# 3-2.net
KiCad netlist of a schematic drawn in Altium Designer
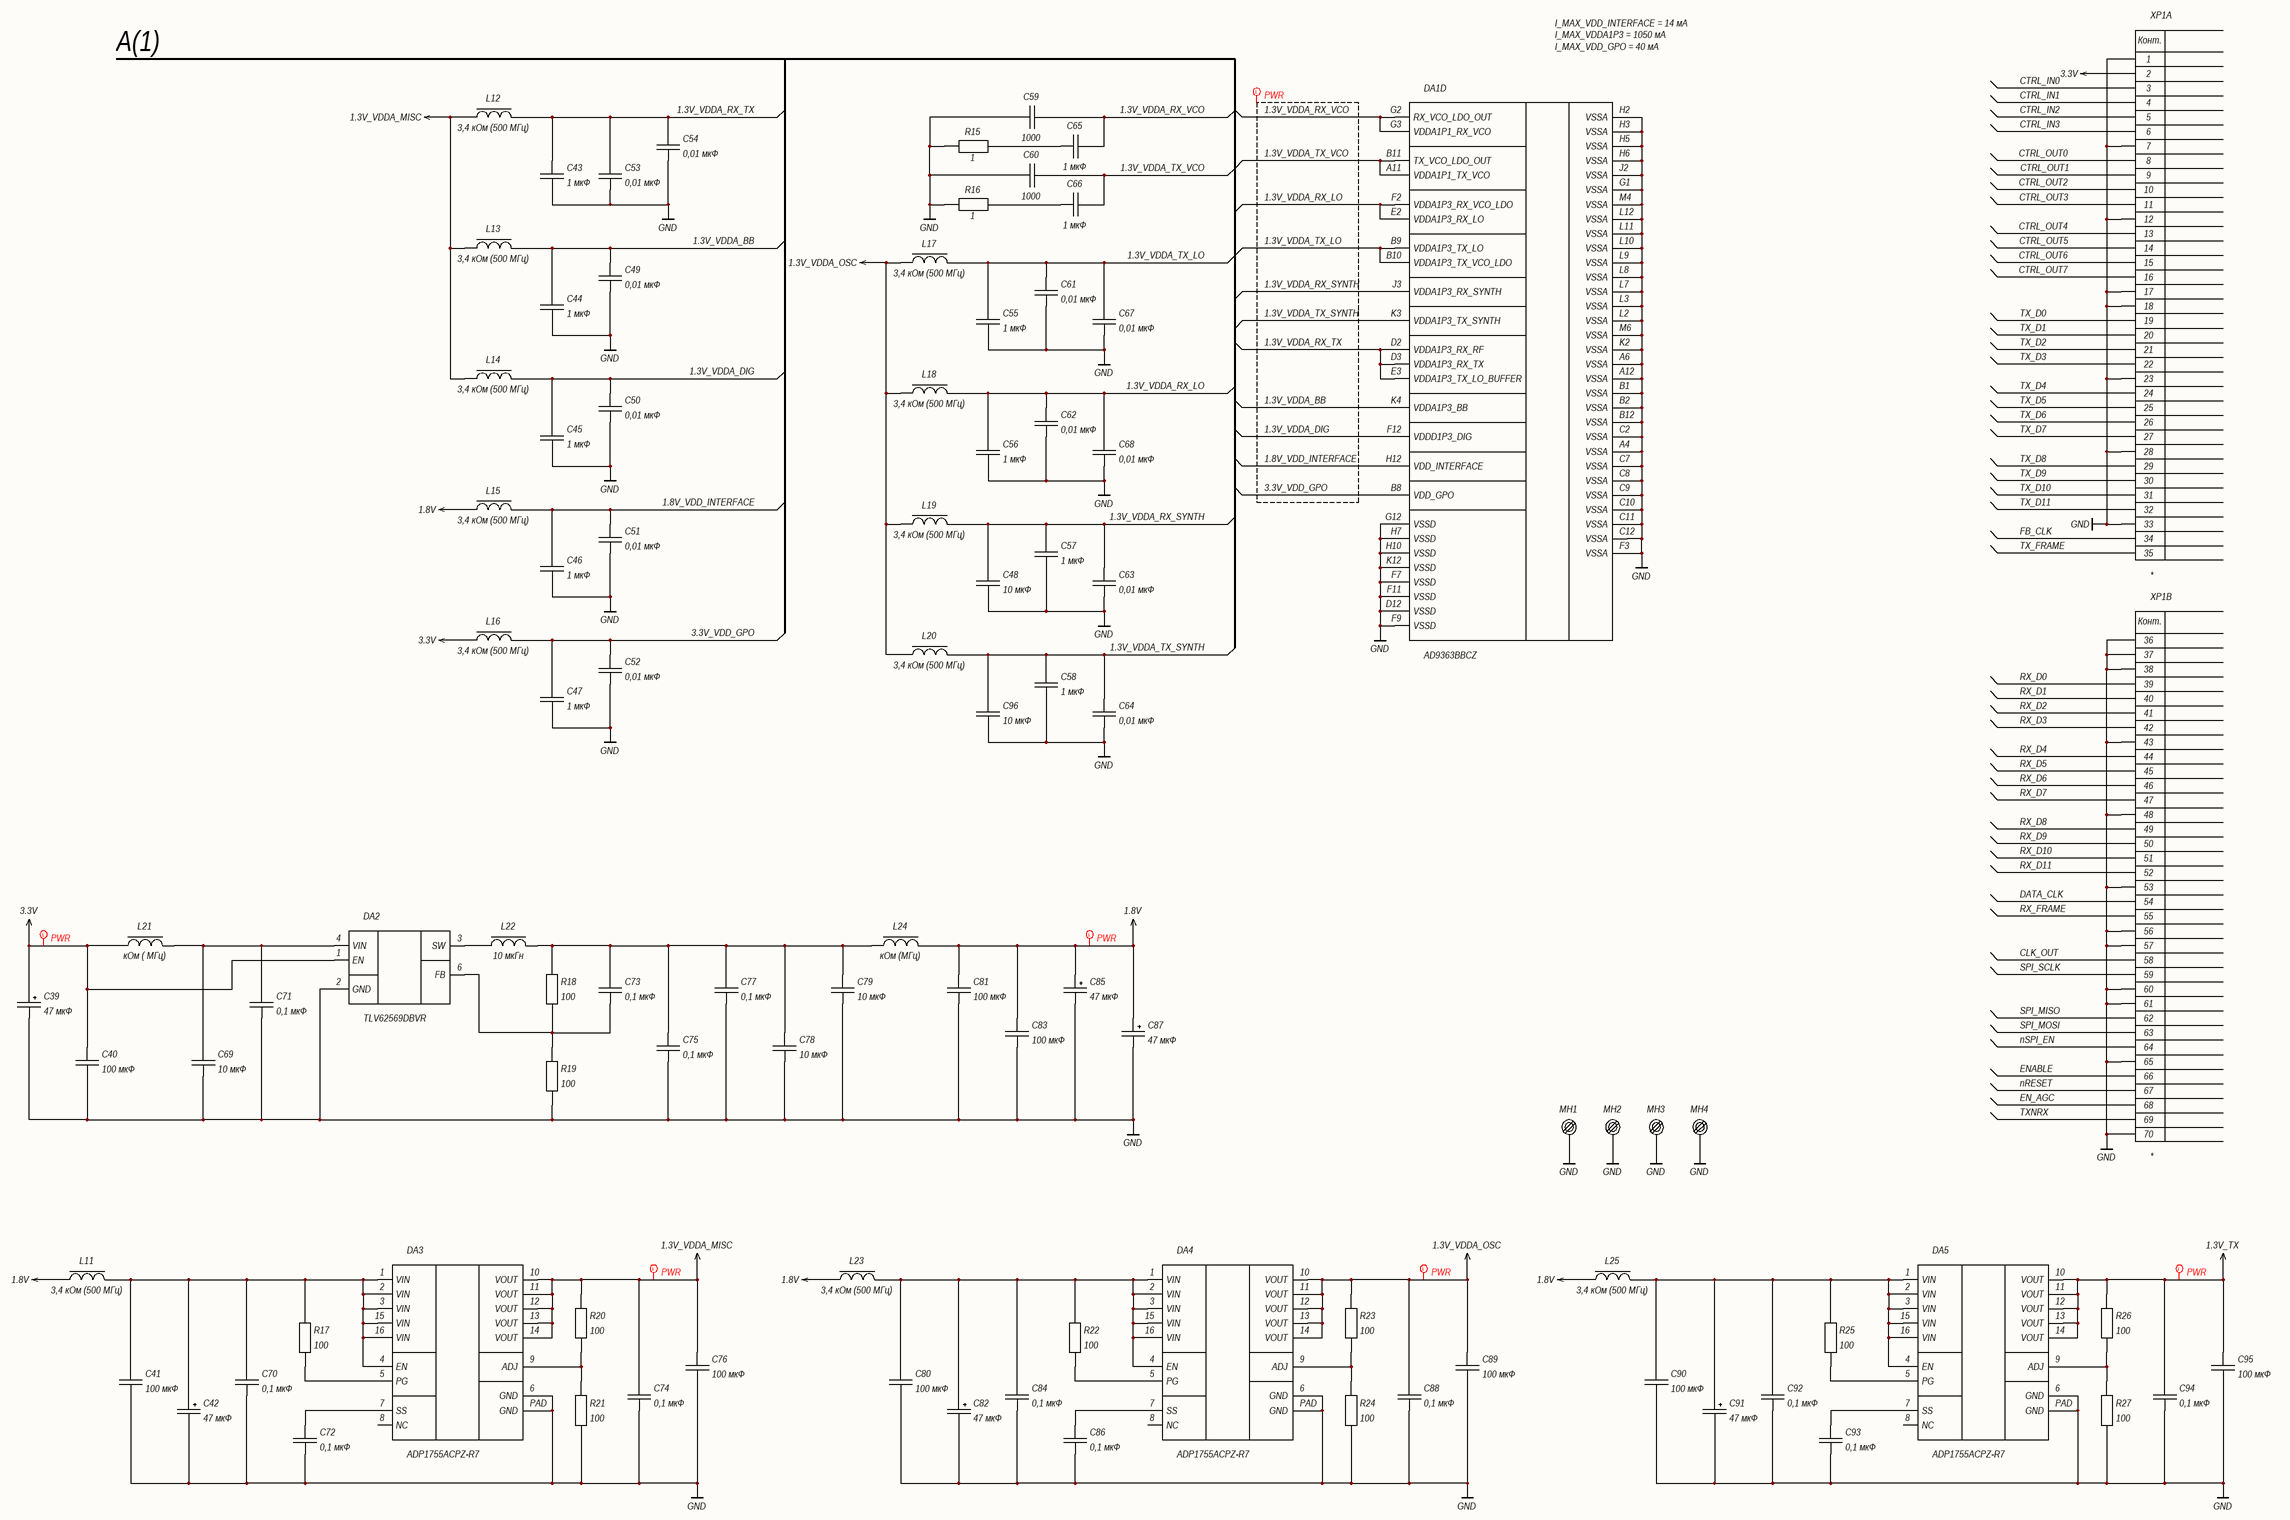
[diagram p0: Э3-2.SchDoc]

(export (version "E")
  (design (tool "Eeschema 10.0.6"))
  (components
    (comp (ref "C39")
      (value "47 мкФ")
      (footprint "TL-A-B-1.8MM")
      (libsource (lib "Capacitors") (part "Polar Ver."))
    )
    (comp (ref "C40")
      (value "100 мкФ")
      (footprint "C1206-B-1.6mm-NO")
      (description "1206 100 мкФ ±20% 6,3 В X5R")
      (libsource (lib "Capacitors") (part "Non Polar Ver."))
    )
    (comp (ref "C41")
      (value "100 мкФ")
      (footprint "C1206-B-1.6mm")
      (description "1206 100 мкФ ±20% 6,3 В X5R")
      (libsource (lib "Capacitors") (part "Non Polar Ver."))
    )
    (comp (ref "C42")
      (value "47 мкФ")
      (footprint "TL-A-B-1.8MM")
      (libsource (lib "Capacitors") (part "Polar Ver."))
    )
    (comp (ref "C43")
      (value "1 мкФ")
      (footprint "C0402-B-0.5mm-NO")
      (description "0402 1 мкФ ±10% 16 В X7R")
      (libsource (lib "Capacitors") (part "Non Polar Ver."))
    )
    (comp (ref "C44")
      (value "1 мкФ")
      (footprint "C0402-B-0.5mm-NO")
      (description "0402 1 мкФ ±10% 16 В X7R")
      (libsource (lib "Capacitors") (part "Non Polar Ver."))
    )
    (comp (ref "C45")
      (value "1 мкФ")
      (footprint "C0402-B-0.5mm-NO")
      (description "0402 1 мкФ ±10% 16 В X7R")
      (libsource (lib "Capacitors") (part "Non Polar Ver."))
    )
    (comp (ref "C46")
      (value "1 мкФ")
      (footprint "C0402-B-0.5mm-NO")
      (description "0402 1 мкФ ±10% 16 В X7R")
      (libsource (lib "Capacitors") (part "Non Polar Ver."))
    )
    (comp (ref "C47")
      (value "1 мкФ")
      (footprint "C0402-B-0.5mm-NO")
      (description "0402 1 мкФ ±10% 16 В X7R")
      (libsource (lib "Capacitors") (part "Non Polar Ver."))
    )
    (comp (ref "C48")
      (value "10 мкФ")
      (footprint "C0603-B-0.8mm-NO")
      (description "0603 10 мкФ ±10% 16 В X7R")
      (libsource (lib "Capacitors") (part "Non Polar Ver."))
    )
    (comp (ref "C49")
      (value "0,01 мкФ")
      (footprint "C0201-B-0.3mm-NO")
      (description "0201 0,01 мкФ ±10% 16 В X7R")
      (libsource (lib "Capacitors") (part "Non Polar Ver."))
    )
    (comp (ref "C50")
      (value "0,01 мкФ")
      (footprint "C0201-B-0.3mm-NO")
      (description "0201 0,01 мкФ ±10% 16 В X7R")
      (libsource (lib "Capacitors") (part "Non Polar Ver."))
    )
    (comp (ref "C51")
      (value "0,01 мкФ")
      (footprint "C0201-B-0.3mm-NO")
      (description "0201 0,01 мкФ ±10% 16 В X7R")
      (libsource (lib "Capacitors") (part "Non Polar Ver."))
    )
    (comp (ref "C52")
      (value "0,01 мкФ")
      (footprint "C0201-B-0.3mm-NO")
      (description "0201 0,01 мкФ ±10% 16 В X7R")
      (libsource (lib "Capacitors") (part "Non Polar Ver."))
    )
    (comp (ref "C53")
      (value "0,01 мкФ")
      (footprint "C0201-B-0.3mm-NO")
      (description "0201 0,01 мкФ ±10% 16 В X7R")
      (libsource (lib "Capacitors") (part "Non Polar Ver."))
    )
    (comp (ref "C54")
      (value "0,01 мкФ")
      (footprint "C0201-B-0.3mm-NO")
      (description "0201 0,01 мкФ ±10% 16 В X7R")
      (libsource (lib "Capacitors") (part "Non Polar Ver."))
    )
    (comp (ref "C55")
      (value "1 мкФ")
      (footprint "C0402-B-0.5mm-NO")
      (description "0402 1 мкФ ±10% 16 В X7R")
      (libsource (lib "Capacitors") (part "Non Polar Ver."))
    )
    (comp (ref "C56")
      (value "1 мкФ")
      (footprint "C0402-B-0.5mm-NO")
      (description "0402 1 мкФ ±10% 16 В X7R")
      (libsource (lib "Capacitors") (part "Non Polar Ver."))
    )
    (comp (ref "C57")
      (value "1 мкФ")
      (footprint "C0402-B-0.5mm-NO")
      (description "0402 1 мкФ ±10% 16 В X7R")
      (libsource (lib "Capacitors") (part "Non Polar Ver."))
    )
    (comp (ref "C58")
      (value "1 мкФ")
      (footprint "C0402-B-0.5mm-NO")
      (description "0402 1 мкФ ±10% 16 В X7R")
      (libsource (lib "Capacitors") (part "Non Polar Ver."))
    )
    (comp (ref "C59")
      (value "1000")
      (footprint "C0201-B-0.3mm-NO")
      (description "0201 1000 пФ ±10% 16 В X7R")
      (libsource (lib "Capacitors") (part "Non Polar Hor."))
    )
    (comp (ref "C60")
      (value "1000")
      (footprint "C0201-B-0.3mm-NO")
      (description "0201 1000 пФ ±10% 16 В X7R")
      (libsource (lib "Capacitors") (part "Non Polar Hor."))
    )
    (comp (ref "C61")
      (value "0,01 мкФ")
      (footprint "C0201-B-0.3mm-NO")
      (description "0201 0,01 мкФ ±10% 16 В X7R")
      (libsource (lib "Capacitors") (part "Non Polar Ver."))
    )
    (comp (ref "C62")
      (value "0,01 мкФ")
      (footprint "C0201-B-0.3mm-NO")
      (description "0201 0,01 мкФ ±10% 16 В X7R")
      (libsource (lib "Capacitors") (part "Non Polar Ver."))
    )
    (comp (ref "C63")
      (value "0,01 мкФ")
      (footprint "C0201-B-0.3mm-NO")
      (description "0201 0,01 мкФ ±10% 16 В X7R")
      (libsource (lib "Capacitors") (part "Non Polar Ver."))
    )
    (comp (ref "C64")
      (value "0,01 мкФ")
      (footprint "C0201-B-0.3mm-NO")
      (description "0201 0,01 мкФ ±10% 16 В X7R")
      (libsource (lib "Capacitors") (part "Non Polar Ver."))
    )
    (comp (ref "C65")
      (value "1 мкФ")
      (footprint "C0402-B-0.5mm-NO")
      (description "0402 1 мкФ ±10% 16 В X7R")
      (libsource (lib "Capacitors") (part "Non Polar Hor."))
    )
    (comp (ref "C66")
      (value "1 мкФ")
      (footprint "C0402-B-0.5mm-NO")
      (description "0402 1 мкФ ±10% 16 В X7R")
      (libsource (lib "Capacitors") (part "Non Polar Hor."))
    )
    (comp (ref "C67")
      (value "0,01 мкФ")
      (footprint "C0201-B-0.3mm-NO")
      (description "0201 0,01 мкФ ±10% 16 В X7R")
      (libsource (lib "Capacitors") (part "Non Polar Ver."))
    )
    (comp (ref "C68")
      (value "0,01 мкФ")
      (footprint "C0201-B-0.3mm-NO")
      (description "0201 0,01 мкФ ±10% 16 В X7R")
      (libsource (lib "Capacitors") (part "Non Polar Ver."))
    )
    (comp (ref "C69")
      (value "10 мкФ")
      (footprint "C0603-B-0.8mm-NO")
      (description "0603 10 мкФ ±10% 16 В X7R")
      (libsource (lib "Capacitors") (part "Non Polar Ver."))
    )
    (comp (ref "C70")
      (value "0,1 мкФ")
      (footprint "C0402-B-0.5mm-NO")
      (description "0402 0,1 мкФ ±10% 16 В X7R")
      (libsource (lib "Capacitors") (part "Non Polar Ver."))
    )
    (comp (ref "C71")
      (value "0,1 мкФ")
      (footprint "C0402-B-0.5mm-NO")
      (description "0402 0,1 мкФ ±10% 16 В X7R")
      (libsource (lib "Capacitors") (part "Non Polar Ver."))
    )
    (comp (ref "C72")
      (value "0,1 мкФ")
      (footprint "C0402-B-0.5mm-NO")
      (description "0402 0,1 мкФ ±10% 16 В X7R")
      (libsource (lib "Capacitors") (part "Non Polar Ver."))
    )
    (comp (ref "C73")
      (value "0,1 мкФ")
      (footprint "C0402-B-0.5mm-NO")
      (description "0402 0,1 мкФ ±10% 16 В X7R")
      (libsource (lib "Capacitors") (part "Non Polar Ver."))
    )
    (comp (ref "C74")
      (value "0,1 мкФ")
      (footprint "C0402-B-0.5mm-NO")
      (description "0402 0,1 мкФ ±10% 16 В X7R")
      (libsource (lib "Capacitors") (part "Non Polar Ver."))
    )
    (comp (ref "C75")
      (value "0,1 мкФ")
      (footprint "C0402-B-0.5mm-NO")
      (description "0402 0,1 мкФ ±10% 16 В X7R")
      (libsource (lib "Capacitors") (part "Non Polar Ver."))
    )
    (comp (ref "C76")
      (value "100 мкФ")
      (footprint "C1206-B-1.6mm")
      (description "1206 100 мкФ ±20% 6,3 В X5R")
      (libsource (lib "Capacitors") (part "Non Polar Ver."))
    )
    (comp (ref "C77")
      (value "0,1 мкФ")
      (footprint "C0402-B-0.5mm-NO")
      (description "0402 0,1 мкФ ±10% 16 В X7R")
      (libsource (lib "Capacitors") (part "Non Polar Ver."))
    )
    (comp (ref "C78")
      (value "10 мкФ")
      (footprint "C0603-B-0.8mm-NO")
      (description "0603 10 мкФ ±10% 16 В X7R")
      (libsource (lib "Capacitors") (part "Non Polar Ver."))
    )
    (comp (ref "C79")
      (value "10 мкФ")
      (footprint "C0603-B-0.8mm-NO")
      (description "0603 10 мкФ ±10% 16 В X7R")
      (libsource (lib "Capacitors") (part "Non Polar Ver."))
    )
    (comp (ref "C80")
      (value "100 мкФ")
      (footprint "C1206-B-1.6mm")
      (description "1206 100 мкФ ±20% 6,3 В X5R")
      (libsource (lib "Capacitors") (part "Non Polar Ver."))
    )
    (comp (ref "C81")
      (value "100 мкФ")
      (footprint "C1206-B-1.6mm-NO")
      (description "1206 100 мкФ ±20% 6,3 В X5R")
      (libsource (lib "Capacitors") (part "Non Polar Ver."))
    )
    (comp (ref "C82")
      (value "47 мкФ")
      (footprint "TL-A-B-1.8MM")
      (libsource (lib "Capacitors") (part "Polar Ver."))
    )
    (comp (ref "C83")
      (value "100 мкФ")
      (footprint "C1206-B-1.6mm-NO")
      (description "1206 100 мкФ ±20% 6,3 В X5R")
      (libsource (lib "Capacitors") (part "Non Polar Ver."))
    )
    (comp (ref "C84")
      (value "0,1 мкФ")
      (footprint "C0402-B-0.5mm-NO")
      (description "0402 0,1 мкФ ±10% 16 В X7R")
      (libsource (lib "Capacitors") (part "Non Polar Ver."))
    )
    (comp (ref "C85")
      (value "47 мкФ")
      (footprint "TL-A-B-1.8MM")
      (libsource (lib "Capacitors") (part "Polar Ver."))
    )
    (comp (ref "C86")
      (value "0,1 мкФ")
      (footprint "C0402-B-0.5mm-NO")
      (description "0402 0,1 мкФ ±10% 16 В X7R")
      (libsource (lib "Capacitors") (part "Non Polar Ver."))
    )
    (comp (ref "C87")
      (value "47 мкФ")
      (footprint "TL-A-B-1.8MM")
      (libsource (lib "Capacitors") (part "Polar Ver."))
    )
    (comp (ref "C88")
      (value "0,1 мкФ")
      (footprint "C0402-B-0.5mm-NO")
      (description "0402 0,1 мкФ ±10% 16 В X7R")
      (libsource (lib "Capacitors") (part "Non Polar Ver."))
    )
    (comp (ref "C89")
      (value "100 мкФ")
      (footprint "C1206-B-1.6mm")
      (description "1206 100 мкФ ±20% 6,3 В X5R")
      (libsource (lib "Capacitors") (part "Non Polar Ver."))
    )
    (comp (ref "C90")
      (value "100 мкФ")
      (footprint "C1206-B-1.6mm")
      (description "1206 100 мкФ ±20% 6,3 В X5R")
      (libsource (lib "Capacitors") (part "Non Polar Ver."))
    )
    (comp (ref "C91")
      (value "47 мкФ")
      (footprint "TL-A-B-1.8MM")
      (libsource (lib "Capacitors") (part "Polar Ver."))
    )
    (comp (ref "C92")
      (value "0,1 мкФ")
      (footprint "C0402-B-0.5mm-NO")
      (description "0402 0,1 мкФ ±10% 16 В X7R")
      (libsource (lib "Capacitors") (part "Non Polar Ver."))
    )
    (comp (ref "C93")
      (value "0,1 мкФ")
      (footprint "C0402-B-0.5mm-NO")
      (description "0402 0,1 мкФ ±10% 16 В X7R")
      (libsource (lib "Capacitors") (part "Non Polar Ver."))
    )
    (comp (ref "C94")
      (value "0,1 мкФ")
      (footprint "C0402-B-0.5mm-NO")
      (description "0402 0,1 мкФ ±10% 16 В X7R")
      (libsource (lib "Capacitors") (part "Non Polar Ver."))
    )
    (comp (ref "C95")
      (value "100 мкФ")
      (footprint "C1206-B-1.6mm")
      (description "1206 100 мкФ ±20% 6,3 В X5R")
      (libsource (lib "Capacitors") (part "Non Polar Ver."))
    )
    (comp (ref "C96")
      (value "10 мкФ")
      (footprint "C0603-B-0.8mm-NO")
      (description "0603 10 мкФ ±10% 16 В X7R")
      (libsource (lib "Capacitors") (part "Non Polar Ver."))
    )
    (comp (ref "DA1")
      (value "AD9363BBCZ")
      (footprint "144-BGA")
      (description "RF Agile Transceiver")
      (fields (field (name "MANUFACTURER") "AnalogDevices"))
      (libsource (lib "Analog") (part "AD9363"))
    )
    (comp (ref "DA2")
      (value "TLV62569DBVR")
      (footprint "SOT-23-5")
      (description "2-A High Efficiency Synchronous Buck Converter in SOT Package")
      (fields (field (name "MANUFACTURER") "Texas Instruments, Inc."))
      (libsource (lib "Power") (part "TLV62569DBV"))
    )
    (comp (ref "DA3")
      (value "ADP1755ACPZ-R7")
      (footprint "16-LFCSP-4-H0.75")
      (description "1.2 A, Ultralow Noise,\r\nHigh PSRR, RF Linear Regulator")
      (fields (field (name "MANUFACTURER") "Analog Devices, Inc."))
      (libsource (lib "Power") (part "ADP1755ACPZ-R7"))
    )
    (comp (ref "DA4")
      (value "ADP1755ACPZ-R7")
      (footprint "16-LFCSP-4-H0.75")
      (description "1.2 A, Ultralow Noise,\r\nHigh PSRR, RF Linear Regulator")
      (fields (field (name "MANUFACTURER") "Analog Devices, Inc."))
      (libsource (lib "Power") (part "ADP1755ACPZ-R7"))
    )
    (comp (ref "DA5")
      (value "ADP1755ACPZ-R7")
      (footprint "16-LFCSP-4-H0.75")
      (description "1.2 A, Ultralow Noise,\r\nHigh PSRR, RF Linear Regulator")
      (fields (field (name "MANUFACTURER") "Analog Devices, Inc."))
      (libsource (lib "Power") (part "ADP1755ACPZ-R7"))
    )
    (comp (ref "L11")
      (value "3,4 кОм (500 МГц)")
      (footprint "L0402-B-0.5mm")
      (fields (field (name "PARTNUMBER") "BLM15HD182BH1"))
      (libsource (lib "Inductors") (part "Inductor MC Hor."))
    )
    (comp (ref "L12")
      (value "3,4 кОм (500 МГц)")
      (footprint "L0402-B-0.5mm-NO")
      (fields (field (name "PARTNUMBER") "BLM15HD182BH1"))
      (libsource (lib "Inductors") (part "Inductor MC Hor."))
    )
    (comp (ref "L13")
      (value "3,4 кОм (500 МГц)")
      (footprint "L0402-B-0.5mm-NO")
      (fields (field (name "PARTNUMBER") "BLM15HD182BH1"))
      (libsource (lib "Inductors") (part "Inductor MC Hor."))
    )
    (comp (ref "L14")
      (value "3,4 кОм (500 МГц)")
      (footprint "L0402-B-0.5mm-NO")
      (fields (field (name "PARTNUMBER") "BLM15HD182BH1"))
      (libsource (lib "Inductors") (part "Inductor MC Hor."))
    )
    (comp (ref "L15")
      (value "3,4 кОм (500 МГц)")
      (footprint "L0402-B-0.5mm-NO")
      (fields (field (name "PARTNUMBER") "BLM15HD182BH1"))
      (libsource (lib "Inductors") (part "Inductor MC Hor."))
    )
    (comp (ref "L16")
      (value "3,4 кОм (500 МГц)")
      (footprint "L0402-B-0.5mm-NO")
      (fields (field (name "PARTNUMBER") "BLM15HD182BH1"))
      (libsource (lib "Inductors") (part "Inductor MC Hor."))
    )
    (comp (ref "L17")
      (value "3,4 кОм (500 МГц)")
      (footprint "L0402-B-0.5mm-NO")
      (fields (field (name "PARTNUMBER") "BLM15HD182BH1"))
      (libsource (lib "Inductors") (part "Inductor MC Hor."))
    )
    (comp (ref "L18")
      (value "3,4 кОм (500 МГц)")
      (footprint "L0402-B-0.5mm-NO")
      (fields (field (name "PARTNUMBER") "BLM15HD182BH1"))
      (libsource (lib "Inductors") (part "Inductor MC Hor."))
    )
    (comp (ref "L19")
      (value "3,4 кОм (500 МГц)")
      (footprint "L0402-B-0.5mm-NO")
      (fields (field (name "PARTNUMBER") "BLM15HD182BH1"))
      (libsource (lib "Inductors") (part "Inductor MC Hor."))
    )
    (comp (ref "L20")
      (value "3,4 кОм (500 МГц)")
      (footprint "L0402-B-0.5mm-NO")
      (fields (field (name "PARTNUMBER") "BLM15HD182BH1"))
      (libsource (lib "Inductors") (part "Inductor MC Hor."))
    )
    (comp (ref "L21")
      (value "кОм ( МГц)")
      (footprint "L0805-B-0.9mm")
      (libsource (lib "Inductors") (part "Inductor MC Hor."))
    )
    (comp (ref "L22")
      (value "10 мкГн")
      (footprint "IHLP-2525CZ-01")
      (fields (field (name "PARTNUMBER") "IHLP2525CZER100M01"))
      (libsource (lib "Inductors") (part "Inductor MC Hor."))
    )
    (comp (ref "L23")
      (value "3,4 кОм (500 МГц)")
      (footprint "L0402-B-0.5mm")
      (fields (field (name "PARTNUMBER") "BLM15HD182BH1"))
      (libsource (lib "Inductors") (part "Inductor MC Hor."))
    )
    (comp (ref "L24")
      (value "кОм (МГц)")
      (footprint "L0805-B-0.9mm")
      (fields (field (name "PARTNUMBER") "BLM15HD182BH1"))
      (libsource (lib "Inductors") (part "Inductor MC Hor."))
    )
    (comp (ref "L25")
      (value "3,4 кОм (500 МГц)")
      (footprint "L0402-B-0.5mm")
      (fields (field (name "PARTNUMBER") "BLM15HD182BH1"))
      (libsource (lib "Inductors") (part "Inductor MC Hor."))
    )
    (comp (ref "MH1")
      (value "Mechanical Connection")
      (footprint "Отверстие 3,2х7")
      (libsource (lib "Mechanics") (part "Mechanical Connection"))
    )
    (comp (ref "MH2")
      (value "Mechanical Connection")
      (footprint "Отверстие 3,2х7")
      (libsource (lib "Mechanics") (part "Mechanical Connection"))
    )
    (comp (ref "MH3")
      (value "Mechanical Connection")
      (footprint "Отверстие 3,2х7")
      (libsource (lib "Mechanics") (part "Mechanical Connection"))
    )
    (comp (ref "MH4")
      (value "Mechanical Connection")
      (footprint "Отверстие 3,2х7")
      (libsource (lib "Mechanics") (part "Mechanical Connection"))
    )
    (comp (ref "R15")
      (value "1")
      (footprint "CR0402-B-0.35mm-NO")
      (description "0402 1 Ом ±1%")
      (libsource (lib "Resistors") (part "Resistor Hor."))
    )
    (comp (ref "R16")
      (value "1")
      (footprint "CR0402-B-0.35mm-NO")
      (description "0402 1 Ом ±1%")
      (libsource (lib "Resistors") (part "Resistor Hor."))
    )
    (comp (ref "R17")
      (value "100")
      (footprint "CR0402-B-0.35mm-NO")
      (description "0402 100 Ом ±1%")
      (libsource (lib "Resistors") (part "Resistor Ver."))
    )
    (comp (ref "R18")
      (value "100")
      (footprint "CR0402-B-0.35mm-NO")
      (description "0402 100 Ом ±1%")
      (libsource (lib "Resistors") (part "Resistor Ver."))
    )
    (comp (ref "R19")
      (value "100")
      (footprint "CR0402-B-0.35mm-NO")
      (description "0402 100 Ом ±1%")
      (libsource (lib "Resistors") (part "Resistor Ver."))
    )
    (comp (ref "R20")
      (value "100")
      (footprint "CR0402-B-0.35mm")
      (description "0402 100 Ом ±1%")
      (libsource (lib "Resistors") (part "Resistor Ver."))
    )
    (comp (ref "R21")
      (value "100")
      (footprint "CR0402-B-0.35mm")
      (description "0402 100 Ом ±1%")
      (libsource (lib "Resistors") (part "Resistor Ver."))
    )
    (comp (ref "R22")
      (value "100")
      (footprint "CR0402-B-0.35mm-NO")
      (description "0402 100 Ом ±1%")
      (libsource (lib "Resistors") (part "Resistor Ver."))
    )
    (comp (ref "R23")
      (value "100")
      (footprint "CR0402-B-0.35mm")
      (description "0402 100 Ом ±1%")
      (libsource (lib "Resistors") (part "Resistor Ver."))
    )
    (comp (ref "R24")
      (value "100")
      (footprint "CR0402-B-0.35mm")
      (description "0402 100 Ом ±1%")
      (libsource (lib "Resistors") (part "Resistor Ver."))
    )
    (comp (ref "R25")
      (value "100")
      (footprint "CR0402-B-0.35mm-NO")
      (description "0402 100 Ом ±1%")
      (libsource (lib "Resistors") (part "Resistor Ver."))
    )
    (comp (ref "R26")
      (value "100")
      (footprint "CR0402-B-0.35mm")
      (description "0402 100 Ом ±1%")
      (libsource (lib "Resistors") (part "Resistor Ver."))
    )
    (comp (ref "R27")
      (value "100")
      (footprint "CR0402-B-0.35mm")
      (description "0402 100 Ом ±1%")
      (libsource (lib "Resistors") (part "Resistor Ver."))
    )
    (comp (ref "XP1")
      (value "*")
      (footprint "PLD1.27-70-NO")
      (libsource (lib "Connectors") (part "XP_70_Pin_Open"))
    )
  )
  (nets
    (net (code "1") (name "/1.3V_VDDA_BB") (class "Default")
      (node (ref "C44") (pin "1") (pinfunction "1_1") (pintype "passive"))
      (node (ref "C49") (pin "1") (pinfunction "1_1") (pintype "passive"))
      (node (ref "DA1") (pin "K4") (pinfunction "VDDA1P3_BB_K4") (pintype "passive"))
      (node (ref "L13") (pin "2") (pinfunction "2_2") (pintype "passive"))
    )
    (net (code "2") (name "/1.3V_VDDA_DIG") (class "Default")
      (node (ref "C45") (pin "1") (pinfunction "1_1") (pintype "passive"))
      (node (ref "C50") (pin "1") (pinfunction "1_1") (pintype "passive"))
      (node (ref "DA1") (pin "F12") (pinfunction "VDDD1P3_DIG_F12") (pintype "passive"))
      (node (ref "L14") (pin "2") (pinfunction "2_2") (pintype "passive"))
    )
    (net (code "3") (name "/1.3V_VDDA_RX_LO") (class "Default")
      (node (ref "C56") (pin "1") (pinfunction "1_1") (pintype "passive"))
      (node (ref "C62") (pin "1") (pinfunction "1_1") (pintype "passive"))
      (node (ref "C68") (pin "1") (pinfunction "1_1") (pintype "passive"))
      (node (ref "DA1") (pin "E2") (pinfunction "VDDA1P3_RX_LO_E2") (pintype "passive"))
      (node (ref "DA1") (pin "F2") (pinfunction "VDDA1P3_RX_VCO_LDO_F2") (pintype "passive"))
      (node (ref "L18") (pin "2") (pinfunction "2_2") (pintype "passive"))
    )
    (net (code "4") (name "/1.3V_VDDA_RX_SYNTH") (class "Default")
      (node (ref "C48") (pin "1") (pinfunction "1_1") (pintype "passive"))
      (node (ref "C57") (pin "1") (pinfunction "1_1") (pintype "passive"))
      (node (ref "C63") (pin "1") (pinfunction "1_1") (pintype "passive"))
      (node (ref "DA1") (pin "J3") (pinfunction "VDDA1P3_RX_SYNTH_J3") (pintype "passive"))
      (node (ref "L19") (pin "2") (pinfunction "2_2") (pintype "passive"))
    )
    (net (code "5") (name "/1.3V_VDDA_RX_TX") (class "Default")
      (node (ref "C43") (pin "1") (pinfunction "1_1") (pintype "passive"))
      (node (ref "C53") (pin "1") (pinfunction "1_1") (pintype "passive"))
      (node (ref "C54") (pin "1") (pinfunction "1_1") (pintype "passive"))
      (node (ref "DA1") (pin "D2") (pinfunction "VDDA1P3_RX_RF_D2") (pintype "passive"))
      (node (ref "DA1") (pin "D3") (pinfunction "VDDA1P3_RX_TX_D3") (pintype "passive"))
      (node (ref "DA1") (pin "E3") (pinfunction "VDDA1P3_TX_LO_BUFFER_E3") (pintype "passive"))
      (node (ref "L12") (pin "2") (pinfunction "2_2") (pintype "passive"))
    )
    (net (code "6") (name "/1.3V_VDDA_RX_VCO") (class "Default")
      (node (ref "C59") (pin "2") (pinfunction "2_2") (pintype "passive"))
      (node (ref "C65") (pin "2") (pinfunction "2_2") (pintype "passive"))
      (node (ref "DA1") (pin "G2") (pinfunction "RX_VCO_LDO_OUT_G2") (pintype "passive"))
      (node (ref "DA1") (pin "G3") (pinfunction "VDDA1P1_RX_VCO_G3") (pintype "passive"))
    )
    (net (code "7") (name "/1.3V_VDDA_TX_LO") (class "Default")
      (node (ref "C55") (pin "1") (pinfunction "1_1") (pintype "passive"))
      (node (ref "C61") (pin "1") (pinfunction "1_1") (pintype "passive"))
      (node (ref "C67") (pin "1") (pinfunction "1_1") (pintype "passive"))
      (node (ref "DA1") (pin "B10") (pinfunction "VDDA1P3_TX_VCO_LDO_B10") (pintype "passive"))
      (node (ref "DA1") (pin "B9") (pinfunction "VDDA1P3_TX_LO_B9") (pintype "passive"))
      (node (ref "L17") (pin "2") (pinfunction "2_2") (pintype "passive"))
    )
    (net (code "8") (name "/1.3V_VDDA_TX_SYNTH") (class "Default")
      (node (ref "C58") (pin "1") (pinfunction "1_1") (pintype "passive"))
      (node (ref "C64") (pin "1") (pinfunction "1_1") (pintype "passive"))
      (node (ref "C96") (pin "1") (pinfunction "1_1") (pintype "passive"))
      (node (ref "DA1") (pin "K3") (pinfunction "VDDA1P3_TX_SYNTH_K3") (pintype "passive"))
      (node (ref "L20") (pin "2") (pinfunction "2_2") (pintype "passive"))
    )
    (net (code "9") (name "/1.3V_VDDA_TX_VCO") (class "Default")
      (node (ref "C60") (pin "2") (pinfunction "2_2") (pintype "passive"))
      (node (ref "C66") (pin "2") (pinfunction "2_2") (pintype "passive"))
      (node (ref "DA1") (pin "A11") (pinfunction "VDDA1P1_TX_VCO_A11") (pintype "passive"))
      (node (ref "DA1") (pin "B11") (pinfunction "TX_VCO_LDO_OUT_B11") (pintype "passive"))
    )
    (net (code "10") (name "/1.8V_VDD_INTERFACE") (class "Default")
      (node (ref "C46") (pin "1") (pinfunction "1_1") (pintype "passive"))
      (node (ref "C51") (pin "1") (pinfunction "1_1") (pintype "passive"))
      (node (ref "DA1") (pin "H12") (pinfunction "VDD_INTERFACE_H12") (pintype "passive"))
      (node (ref "L15") (pin "2") (pinfunction "2_2") (pintype "passive"))
    )
    (net (code "11") (name "/3.3V_VDD_GPO") (class "Default")
      (node (ref "C47") (pin "1") (pinfunction "1_1") (pintype "passive"))
      (node (ref "C52") (pin "1") (pinfunction "1_1") (pintype "passive"))
      (node (ref "DA1") (pin "B8") (pinfunction "VDD_GPO_B8") (pintype "passive"))
      (node (ref "L16") (pin "2") (pinfunction "2_2") (pintype "passive"))
    )
    (net (code "12") (name "/CLK_OUT") (class "Default")
      (node (ref "XP1") (pin "58") (pinfunction "58_58") (pintype "passive"))
    )
    (net (code "13") (name "/CTRL_IN0") (class "Default")
      (node (ref "XP1") (pin "3") (pinfunction "3_3") (pintype "passive"))
    )
    (net (code "14") (name "/CTRL_IN1") (class "Default")
      (node (ref "XP1") (pin "4") (pinfunction "4_4") (pintype "passive"))
    )
    (net (code "15") (name "/CTRL_IN2") (class "Default")
      (node (ref "XP1") (pin "5") (pinfunction "5_5") (pintype "passive"))
    )
    (net (code "16") (name "/CTRL_IN3") (class "Default")
      (node (ref "XP1") (pin "6") (pinfunction "6_6") (pintype "passive"))
    )
    (net (code "17") (name "/CTRL_OUT0") (class "Default")
      (node (ref "XP1") (pin "8") (pinfunction "8_8") (pintype "passive"))
    )
    (net (code "18") (name "/CTRL_OUT1") (class "Default")
      (node (ref "XP1") (pin "9") (pinfunction "9_9") (pintype "passive"))
    )
    (net (code "19") (name "/CTRL_OUT2") (class "Default")
      (node (ref "XP1") (pin "10") (pinfunction "10_10") (pintype "passive"))
    )
    (net (code "20") (name "/CTRL_OUT3") (class "Default")
      (node (ref "XP1") (pin "11") (pinfunction "11_11") (pintype "passive"))
    )
    (net (code "21") (name "/CTRL_OUT4") (class "Default")
      (node (ref "XP1") (pin "13") (pinfunction "13_13") (pintype "passive"))
    )
    (net (code "22") (name "/CTRL_OUT5") (class "Default")
      (node (ref "XP1") (pin "14") (pinfunction "14_14") (pintype "passive"))
    )
    (net (code "23") (name "/CTRL_OUT6") (class "Default")
      (node (ref "XP1") (pin "15") (pinfunction "15_15") (pintype "passive"))
    )
    (net (code "24") (name "/CTRL_OUT7") (class "Default")
      (node (ref "XP1") (pin "16") (pinfunction "16_16") (pintype "passive"))
    )
    (net (code "25") (name "/DATA_CLK") (class "Default")
      (node (ref "XP1") (pin "54") (pinfunction "54_54") (pintype "passive"))
    )
    (net (code "26") (name "/ENABLE") (class "Default")
      (node (ref "XP1") (pin "66") (pinfunction "66_66") (pintype "passive"))
    )
    (net (code "27") (name "/EN_AGC") (class "Default")
      (node (ref "XP1") (pin "68") (pinfunction "68_68") (pintype "passive"))
    )
    (net (code "28") (name "/FB_CLK") (class "Default")
      (node (ref "XP1") (pin "34") (pinfunction "34_34") (pintype "passive"))
    )
    (net (code "29") (name "/RX_D0") (class "Default")
      (node (ref "XP1") (pin "39") (pinfunction "39_39") (pintype "passive"))
    )
    (net (code "30") (name "/RX_D1") (class "Default")
      (node (ref "XP1") (pin "40") (pinfunction "40_40") (pintype "passive"))
    )
    (net (code "31") (name "/RX_D2") (class "Default")
      (node (ref "XP1") (pin "41") (pinfunction "41_41") (pintype "passive"))
    )
    (net (code "32") (name "/RX_D3") (class "Default")
      (node (ref "XP1") (pin "42") (pinfunction "42_42") (pintype "passive"))
    )
    (net (code "33") (name "/RX_D4") (class "Default")
      (node (ref "XP1") (pin "44") (pinfunction "44_44") (pintype "passive"))
    )
    (net (code "34") (name "/RX_D5") (class "Default")
      (node (ref "XP1") (pin "45") (pinfunction "45_45") (pintype "passive"))
    )
    (net (code "35") (name "/RX_D6") (class "Default")
      (node (ref "XP1") (pin "46") (pinfunction "46_46") (pintype "passive"))
    )
    (net (code "36") (name "/RX_D7") (class "Default")
      (node (ref "XP1") (pin "47") (pinfunction "47_47") (pintype "passive"))
    )
    (net (code "37") (name "/RX_D8") (class "Default")
      (node (ref "XP1") (pin "49") (pinfunction "49_49") (pintype "passive"))
    )
    (net (code "38") (name "/RX_D9") (class "Default")
      (node (ref "XP1") (pin "50") (pinfunction "50_50") (pintype "passive"))
    )
    (net (code "39") (name "/RX_D10") (class "Default")
      (node (ref "XP1") (pin "51") (pinfunction "51_51") (pintype "passive"))
    )
    (net (code "40") (name "/RX_D11") (class "Default")
      (node (ref "XP1") (pin "52") (pinfunction "52_52") (pintype "passive"))
    )
    (net (code "41") (name "/RX_FRAME") (class "Default")
      (node (ref "XP1") (pin "55") (pinfunction "55_55") (pintype "passive"))
    )
    (net (code "42") (name "/SPI_MISO") (class "Default")
      (node (ref "XP1") (pin "62") (pinfunction "62_62") (pintype "passive"))
    )
    (net (code "43") (name "/SPI_MOSI") (class "Default")
      (node (ref "XP1") (pin "63") (pinfunction "63_63") (pintype "passive"))
    )
    (net (code "44") (name "/SPI_SCLK") (class "Default")
      (node (ref "XP1") (pin "59") (pinfunction "59_59") (pintype "passive"))
    )
    (net (code "45") (name "/TXNRX") (class "Default")
      (node (ref "XP1") (pin "69") (pinfunction "69_69") (pintype "passive"))
    )
    (net (code "46") (name "/TX_D0") (class "Default")
      (node (ref "XP1") (pin "19") (pinfunction "19_19") (pintype "passive"))
    )
    (net (code "47") (name "/TX_D1") (class "Default")
      (node (ref "XP1") (pin "20") (pinfunction "20_20") (pintype "passive"))
    )
    (net (code "48") (name "/TX_D2") (class "Default")
      (node (ref "XP1") (pin "21") (pinfunction "21_21") (pintype "passive"))
    )
    (net (code "49") (name "/TX_D3") (class "Default")
      (node (ref "XP1") (pin "22") (pinfunction "22_22") (pintype "passive"))
    )
    (net (code "50") (name "/TX_D4") (class "Default")
      (node (ref "XP1") (pin "24") (pinfunction "24_24") (pintype "passive"))
    )
    (net (code "51") (name "/TX_D5") (class "Default")
      (node (ref "XP1") (pin "25") (pinfunction "25_25") (pintype "passive"))
    )
    (net (code "52") (name "/TX_D6") (class "Default")
      (node (ref "XP1") (pin "26") (pinfunction "26_26") (pintype "passive"))
    )
    (net (code "53") (name "/TX_D7") (class "Default")
      (node (ref "XP1") (pin "27") (pinfunction "27_27") (pintype "passive"))
    )
    (net (code "54") (name "/TX_D8") (class "Default")
      (node (ref "XP1") (pin "29") (pinfunction "29_29") (pintype "passive"))
    )
    (net (code "55") (name "/TX_D9") (class "Default")
      (node (ref "XP1") (pin "30") (pinfunction "30_30") (pintype "passive"))
    )
    (net (code "56") (name "/TX_D10") (class "Default")
      (node (ref "XP1") (pin "31") (pinfunction "31_31") (pintype "passive"))
    )
    (net (code "57") (name "/TX_D11") (class "Default")
      (node (ref "XP1") (pin "32") (pinfunction "32_32") (pintype "passive"))
    )
    (net (code "58") (name "/TX_FRAME") (class "Default")
      (node (ref "XP1") (pin "35") (pinfunction "35_35") (pintype "passive"))
    )
    (net (code "59") (name "/nRESET") (class "Default")
      (node (ref "XP1") (pin "67") (pinfunction "67_67") (pintype "passive"))
    )
    (net (code "60") (name "/nSPI_EN") (class "Default")
      (node (ref "XP1") (pin "64") (pinfunction "64_64") (pintype "passive"))
    )
    (net (code "61") (name "1.3V_TX") (class "Default")
      (node (ref "C94") (pin "1") (pinfunction "1_1") (pintype "passive"))
      (node (ref "C95") (pin "1") (pinfunction "1_1") (pintype "passive"))
      (node (ref "DA5") (pin "10") (pinfunction "VOUT_10") (pintype "passive"))
      (node (ref "DA5") (pin "11") (pinfunction "VOUT_11") (pintype "passive"))
      (node (ref "DA5") (pin "12") (pinfunction "VOUT_12") (pintype "passive"))
      (node (ref "DA5") (pin "13") (pinfunction "VOUT_13") (pintype "passive"))
      (node (ref "DA5") (pin "14") (pinfunction "VOUT_14") (pintype "passive"))
      (node (ref "R26") (pin "1") (pinfunction "1_1") (pintype "passive"))
    )
    (net (code "62") (name "1.3V_VDDA_MISC") (class "Default")
      (node (ref "C74") (pin "1") (pinfunction "1_1") (pintype "passive"))
      (node (ref "C76") (pin "1") (pinfunction "1_1") (pintype "passive"))
      (node (ref "DA3") (pin "10") (pinfunction "VOUT_10") (pintype "passive"))
      (node (ref "DA3") (pin "11") (pinfunction "VOUT_11") (pintype "passive"))
      (node (ref "DA3") (pin "12") (pinfunction "VOUT_12") (pintype "passive"))
      (node (ref "DA3") (pin "13") (pinfunction "VOUT_13") (pintype "passive"))
      (node (ref "DA3") (pin "14") (pinfunction "VOUT_14") (pintype "passive"))
      (node (ref "L12") (pin "1") (pinfunction "1_1") (pintype "passive"))
      (node (ref "L13") (pin "1") (pinfunction "1_1") (pintype "passive"))
      (node (ref "L14") (pin "1") (pinfunction "1_1") (pintype "passive"))
      (node (ref "R20") (pin "1") (pinfunction "1_1") (pintype "passive"))
    )
    (net (code "63") (name "1.3V_VDDA_OSC") (class "Default")
      (node (ref "C88") (pin "1") (pinfunction "1_1") (pintype "passive"))
      (node (ref "C89") (pin "1") (pinfunction "1_1") (pintype "passive"))
      (node (ref "DA4") (pin "10") (pinfunction "VOUT_10") (pintype "passive"))
      (node (ref "DA4") (pin "11") (pinfunction "VOUT_11") (pintype "passive"))
      (node (ref "DA4") (pin "12") (pinfunction "VOUT_12") (pintype "passive"))
      (node (ref "DA4") (pin "13") (pinfunction "VOUT_13") (pintype "passive"))
      (node (ref "DA4") (pin "14") (pinfunction "VOUT_14") (pintype "passive"))
      (node (ref "L17") (pin "1") (pinfunction "1_1") (pintype "passive"))
      (node (ref "L18") (pin "1") (pinfunction "1_1") (pintype "passive"))
      (node (ref "L19") (pin "1") (pinfunction "1_1") (pintype "passive"))
      (node (ref "L20") (pin "1") (pinfunction "1_1") (pintype "passive"))
      (node (ref "R23") (pin "1") (pinfunction "1_1") (pintype "passive"))
    )
    (net (code "64") (name "1.8V") (class "Default")
      (node (ref "C81") (pin "1") (pinfunction "1_1") (pintype "passive"))
      (node (ref "C83") (pin "1") (pinfunction "1_1") (pintype "passive"))
      (node (ref "C85") (pin "1") (pinfunction "1_1") (pintype "passive"))
      (node (ref "C87") (pin "1") (pinfunction "1_1") (pintype "passive"))
      (node (ref "L11") (pin "1") (pinfunction "1_1") (pintype "passive"))
      (node (ref "L15") (pin "1") (pinfunction "1_1") (pintype "passive"))
      (node (ref "L23") (pin "1") (pinfunction "1_1") (pintype "passive"))
      (node (ref "L24") (pin "2") (pinfunction "2_2") (pintype "passive"))
      (node (ref "L25") (pin "1") (pinfunction "1_1") (pintype "passive"))
    )
    (net (code "65") (name "3.3V") (class "Default")
      (node (ref "C39") (pin "1") (pinfunction "1_1") (pintype "passive"))
      (node (ref "C40") (pin "1") (pinfunction "1_1") (pintype "passive"))
      (node (ref "DA2") (pin "1") (pinfunction "EN_1") (pintype "passive"))
      (node (ref "L16") (pin "1") (pinfunction "1_1") (pintype "passive"))
      (node (ref "L21") (pin "1") (pinfunction "1_1") (pintype "passive"))
      (node (ref "XP1") (pin "2") (pinfunction "2_2") (pintype "passive"))
    )
    (net (code "66") (name "GND") (class "Default")
      (node (ref "C39") (pin "2") (pinfunction "2_2") (pintype "passive"))
      (node (ref "C40") (pin "2") (pinfunction "2_2") (pintype "passive"))
      (node (ref "C41") (pin "2") (pinfunction "2_2") (pintype "passive"))
      (node (ref "C42") (pin "2") (pinfunction "2_2") (pintype "passive"))
      (node (ref "C43") (pin "2") (pinfunction "2_2") (pintype "passive"))
      (node (ref "C44") (pin "2") (pinfunction "2_2") (pintype "passive"))
      (node (ref "C45") (pin "2") (pinfunction "2_2") (pintype "passive"))
      (node (ref "C46") (pin "2") (pinfunction "2_2") (pintype "passive"))
      (node (ref "C47") (pin "2") (pinfunction "2_2") (pintype "passive"))
      (node (ref "C48") (pin "2") (pinfunction "2_2") (pintype "passive"))
      (node (ref "C49") (pin "2") (pinfunction "2_2") (pintype "passive"))
      (node (ref "C50") (pin "2") (pinfunction "2_2") (pintype "passive"))
      (node (ref "C51") (pin "2") (pinfunction "2_2") (pintype "passive"))
      (node (ref "C52") (pin "2") (pinfunction "2_2") (pintype "passive"))
      (node (ref "C53") (pin "2") (pinfunction "2_2") (pintype "passive"))
      (node (ref "C54") (pin "2") (pinfunction "2_2") (pintype "passive"))
      (node (ref "C55") (pin "2") (pinfunction "2_2") (pintype "passive"))
      (node (ref "C56") (pin "2") (pinfunction "2_2") (pintype "passive"))
      (node (ref "C57") (pin "2") (pinfunction "2_2") (pintype "passive"))
      (node (ref "C58") (pin "2") (pinfunction "2_2") (pintype "passive"))
      (node (ref "C59") (pin "1") (pinfunction "1_1") (pintype "passive"))
      (node (ref "C60") (pin "1") (pinfunction "1_1") (pintype "passive"))
      (node (ref "C61") (pin "2") (pinfunction "2_2") (pintype "passive"))
      (node (ref "C62") (pin "2") (pinfunction "2_2") (pintype "passive"))
      (node (ref "C63") (pin "2") (pinfunction "2_2") (pintype "passive"))
      (node (ref "C64") (pin "2") (pinfunction "2_2") (pintype "passive"))
      (node (ref "C67") (pin "2") (pinfunction "2_2") (pintype "passive"))
      (node (ref "C68") (pin "2") (pinfunction "2_2") (pintype "passive"))
      (node (ref "C69") (pin "2") (pinfunction "2_2") (pintype "passive"))
      (node (ref "C70") (pin "2") (pinfunction "2_2") (pintype "passive"))
      (node (ref "C71") (pin "2") (pinfunction "2_2") (pintype "passive"))
      (node (ref "C72") (pin "2") (pinfunction "2_2") (pintype "passive"))
      (node (ref "C74") (pin "2") (pinfunction "2_2") (pintype "passive"))
      (node (ref "C75") (pin "2") (pinfunction "2_2") (pintype "passive"))
      (node (ref "C76") (pin "2") (pinfunction "2_2") (pintype "passive"))
      (node (ref "C77") (pin "2") (pinfunction "2_2") (pintype "passive"))
      (node (ref "C78") (pin "2") (pinfunction "2_2") (pintype "passive"))
      (node (ref "C79") (pin "2") (pinfunction "2_2") (pintype "passive"))
      (node (ref "C80") (pin "2") (pinfunction "2_2") (pintype "passive"))
      (node (ref "C81") (pin "2") (pinfunction "2_2") (pintype "passive"))
      (node (ref "C82") (pin "2") (pinfunction "2_2") (pintype "passive"))
      (node (ref "C83") (pin "2") (pinfunction "2_2") (pintype "passive"))
      (node (ref "C84") (pin "2") (pinfunction "2_2") (pintype "passive"))
      (node (ref "C85") (pin "2") (pinfunction "2_2") (pintype "passive"))
      (node (ref "C86") (pin "2") (pinfunction "2_2") (pintype "passive"))
      (node (ref "C87") (pin "2") (pinfunction "2_2") (pintype "passive"))
      (node (ref "C88") (pin "2") (pinfunction "2_2") (pintype "passive"))
      (node (ref "C89") (pin "2") (pinfunction "2_2") (pintype "passive"))
      (node (ref "C90") (pin "2") (pinfunction "2_2") (pintype "passive"))
      (node (ref "C91") (pin "2") (pinfunction "2_2") (pintype "passive"))
      (node (ref "C92") (pin "2") (pinfunction "2_2") (pintype "passive"))
      (node (ref "C93") (pin "2") (pinfunction "2_2") (pintype "passive"))
      (node (ref "C94") (pin "2") (pinfunction "2_2") (pintype "passive"))
      (node (ref "C95") (pin "2") (pinfunction "2_2") (pintype "passive"))
      (node (ref "C96") (pin "2") (pinfunction "2_2") (pintype "passive"))
      (node (ref "DA1") (pin "A12") (pinfunction "VSSA_A12") (pintype "passive"))
      (node (ref "DA1") (pin "A4") (pinfunction "VSSA_A4") (pintype "passive"))
      (node (ref "DA1") (pin "A6") (pinfunction "VSSA_A6") (pintype "passive"))
      (node (ref "DA1") (pin "B1") (pinfunction "VSSA_B1") (pintype "passive"))
      (node (ref "DA1") (pin "B12") (pinfunction "VSSA_B12") (pintype "passive"))
      (node (ref "DA1") (pin "B2") (pinfunction "VSSA_B2") (pintype "passive"))
      (node (ref "DA1") (pin "C10") (pinfunction "VSSA_C10") (pintype "passive"))
      (node (ref "DA1") (pin "C11") (pinfunction "VSSA_C11") (pintype "passive"))
      (node (ref "DA1") (pin "C12") (pinfunction "VSSA_C12") (pintype "passive"))
      (node (ref "DA1") (pin "C2") (pinfunction "VSSA_C2") (pintype "passive"))
      (node (ref "DA1") (pin "C7") (pinfunction "VSSA_C7") (pintype "passive"))
      (node (ref "DA1") (pin "C8") (pinfunction "VSSA_C8") (pintype "passive"))
      (node (ref "DA1") (pin "C9") (pinfunction "VSSA_C9") (pintype "passive"))
      (node (ref "DA1") (pin "D12") (pinfunction "VSSD_D12") (pintype "passive"))
      (node (ref "DA1") (pin "F11") (pinfunction "VSSD_F11") (pintype "passive"))
      (node (ref "DA1") (pin "F3") (pinfunction "VSSA_F3") (pintype "passive"))
      (node (ref "DA1") (pin "F7") (pinfunction "VSSD_F7") (pintype "passive"))
      (node (ref "DA1") (pin "F9") (pinfunction "VSSD_F9") (pintype "passive"))
      (node (ref "DA1") (pin "G1") (pinfunction "VSSA_G1") (pintype "passive"))
      (node (ref "DA1") (pin "G12") (pinfunction "VSSD_G12") (pintype "passive"))
      (node (ref "DA1") (pin "H10") (pinfunction "VSSD_H10") (pintype "passive"))
      (node (ref "DA1") (pin "H2") (pinfunction "VSSA_H2") (pintype "passive"))
      (node (ref "DA1") (pin "H3") (pinfunction "VSSA_H3") (pintype "passive"))
      (node (ref "DA1") (pin "H5") (pinfunction "VSSA_H5") (pintype "passive"))
      (node (ref "DA1") (pin "H6") (pinfunction "VSSA_H6") (pintype "passive"))
      (node (ref "DA1") (pin "H7") (pinfunction "VSSD_H7") (pintype "passive"))
      (node (ref "DA1") (pin "J2") (pinfunction "VSSA_J2") (pintype "passive"))
      (node (ref "DA1") (pin "K12") (pinfunction "VSSD_K12") (pintype "passive"))
      (node (ref "DA1") (pin "K2") (pinfunction "VSSA_K2") (pintype "passive"))
      (node (ref "DA1") (pin "L10") (pinfunction "VSSA_L10") (pintype "passive"))
      (node (ref "DA1") (pin "L11") (pinfunction "VSSA_L11") (pintype "passive"))
      (node (ref "DA1") (pin "L12") (pinfunction "VSSA_L12") (pintype "passive"))
      (node (ref "DA1") (pin "L2") (pinfunction "VSSA_L2") (pintype "passive"))
      (node (ref "DA1") (pin "L3") (pinfunction "VSSA_L3") (pintype "passive"))
      (node (ref "DA1") (pin "L7") (pinfunction "VSSA_L7") (pintype "passive"))
      (node (ref "DA1") (pin "L8") (pinfunction "VSSA_L8") (pintype "passive"))
      (node (ref "DA1") (pin "L9") (pinfunction "VSSA_L9") (pintype "passive"))
      (node (ref "DA1") (pin "M4") (pinfunction "VSSA_M4") (pintype "passive"))
      (node (ref "DA1") (pin "M6") (pinfunction "VSSA_M6") (pintype "passive"))
      (node (ref "DA2") (pin "2") (pinfunction "GND_2") (pintype "passive"))
      (node (ref "DA3") (pin "6") (pinfunction "GND_6") (pintype "passive"))
      (node (ref "DA3") (pin "PAD") (pinfunction "GND_PAD") (pintype "passive"))
      (node (ref "DA4") (pin "6") (pinfunction "GND_6") (pintype "passive"))
      (node (ref "DA4") (pin "PAD") (pinfunction "GND_PAD") (pintype "passive"))
      (node (ref "DA5") (pin "6") (pinfunction "GND_6") (pintype "passive"))
      (node (ref "DA5") (pin "PAD") (pinfunction "GND_PAD") (pintype "passive"))
      (node (ref "MH1") (pin "0") (pinfunction "0_0") (pintype "passive"))
      (node (ref "MH2") (pin "0") (pinfunction "0_0") (pintype "passive"))
      (node (ref "MH3") (pin "0") (pinfunction "0_0") (pintype "passive"))
      (node (ref "MH4") (pin "0") (pinfunction "0_0") (pintype "passive"))
      (node (ref "R15") (pin "1") (pinfunction "1_1") (pintype "passive"))
      (node (ref "R16") (pin "1") (pinfunction "1_1") (pintype "passive"))
      (node (ref "R19") (pin "2") (pinfunction "2_2") (pintype "passive"))
      (node (ref "R21") (pin "2") (pinfunction "2_2") (pintype "passive"))
      (node (ref "R24") (pin "2") (pinfunction "2_2") (pintype "passive"))
      (node (ref "R27") (pin "2") (pinfunction "2_2") (pintype "passive"))
      (node (ref "XP1") (pin "1") (pinfunction "1_1") (pintype "passive"))
      (node (ref "XP1") (pin "12") (pinfunction "12_12") (pintype "passive"))
      (node (ref "XP1") (pin "17") (pinfunction "17_17") (pintype "passive"))
      (node (ref "XP1") (pin "18") (pinfunction "18_18") (pintype "passive"))
      (node (ref "XP1") (pin "23") (pinfunction "23_23") (pintype "passive"))
      (node (ref "XP1") (pin "28") (pinfunction "28_28") (pintype "passive"))
      (node (ref "XP1") (pin "33") (pinfunction "33_33") (pintype "passive"))
      (node (ref "XP1") (pin "36") (pinfunction "36_36") (pintype "passive"))
      (node (ref "XP1") (pin "37") (pinfunction "37_37") (pintype "passive"))
      (node (ref "XP1") (pin "38") (pinfunction "38_38") (pintype "passive"))
      (node (ref "XP1") (pin "43") (pinfunction "43_43") (pintype "passive"))
      (node (ref "XP1") (pin "48") (pinfunction "48_48") (pintype "passive"))
      (node (ref "XP1") (pin "53") (pinfunction "53_53") (pintype "passive"))
      (node (ref "XP1") (pin "56") (pinfunction "56_56") (pintype "passive"))
      (node (ref "XP1") (pin "57") (pinfunction "57_57") (pintype "passive"))
      (node (ref "XP1") (pin "60") (pinfunction "60_60") (pintype "passive"))
      (node (ref "XP1") (pin "61") (pinfunction "61_61") (pintype "passive"))
      (node (ref "XP1") (pin "65") (pinfunction "65_65") (pintype "passive"))
      (node (ref "XP1") (pin "7") (pinfunction "7_7") (pintype "passive"))
      (node (ref "XP1") (pin "70") (pinfunction "70_70") (pintype "passive"))
    )
    (net (code "67") (name "Net-(C65-Pad1)") (class "Default")
      (node (ref "C65") (pin "1") (pinfunction "1_1") (pintype "passive"))
      (node (ref "R15") (pin "2") (pinfunction "2_2") (pintype "passive"))
    )
    (net (code "68") (name "Net-(C66-Pad1)") (class "Default")
      (node (ref "C66") (pin "1") (pinfunction "1_1") (pintype "passive"))
      (node (ref "R16") (pin "2") (pinfunction "2_2") (pintype "passive"))
    )
    (net (code "69") (name "Net-(C73-Pad1)") (class "Default")
      (node (ref "C73") (pin "1") (pinfunction "1_1") (pintype "passive"))
      (node (ref "C75") (pin "1") (pinfunction "1_1") (pintype "passive"))
      (node (ref "C77") (pin "1") (pinfunction "1_1") (pintype "passive"))
      (node (ref "C78") (pin "1") (pinfunction "1_1") (pintype "passive"))
      (node (ref "C79") (pin "1") (pinfunction "1_1") (pintype "passive"))
      (node (ref "L22") (pin "2") (pinfunction "2_2") (pintype "passive"))
      (node (ref "L24") (pin "1") (pinfunction "1_1") (pintype "passive"))
      (node (ref "R18") (pin "1") (pinfunction "1_1") (pintype "passive"))
    )
    (net (code "70") (name "Net-(DA2-FB)") (class "Default")
      (node (ref "C73") (pin "2") (pinfunction "2_2") (pintype "passive"))
      (node (ref "DA2") (pin "6") (pinfunction "FB_6") (pintype "passive"))
      (node (ref "R18") (pin "2") (pinfunction "2_2") (pintype "passive"))
      (node (ref "R19") (pin "1") (pinfunction "1_1") (pintype "passive"))
    )
    (net (code "71") (name "Net-(DA2-SW)") (class "Default")
      (node (ref "DA2") (pin "3") (pinfunction "SW_3") (pintype "passive"))
      (node (ref "L22") (pin "1") (pinfunction "1_1") (pintype "passive"))
    )
    (net (code "72") (name "Net-(DA2-VIN)") (class "Default")
      (node (ref "C69") (pin "1") (pinfunction "1_1") (pintype "passive"))
      (node (ref "C71") (pin "1") (pinfunction "1_1") (pintype "passive"))
      (node (ref "DA2") (pin "4") (pinfunction "VIN_4") (pintype "passive"))
      (node (ref "L21") (pin "2") (pinfunction "2_2") (pintype "passive"))
    )
    (net (code "73") (name "Net-(DA3-ADJ)") (class "Default")
      (node (ref "DA3") (pin "9") (pinfunction "ADJ_9") (pintype "passive"))
      (node (ref "R20") (pin "2") (pinfunction "2_2") (pintype "passive"))
      (node (ref "R21") (pin "1") (pinfunction "1_1") (pintype "passive"))
    )
    (net (code "74") (name "Net-(DA3-EN)") (class "Default")
      (node (ref "C41") (pin "1") (pinfunction "1_1") (pintype "passive"))
      (node (ref "C42") (pin "1") (pinfunction "1_1") (pintype "passive"))
      (node (ref "C70") (pin "1") (pinfunction "1_1") (pintype "passive"))
      (node (ref "DA3") (pin "1") (pinfunction "VIN_1") (pintype "passive"))
      (node (ref "DA3") (pin "15") (pinfunction "VIN_15") (pintype "passive"))
      (node (ref "DA3") (pin "16") (pinfunction "VIN_16") (pintype "passive"))
      (node (ref "DA3") (pin "2") (pinfunction "VIN_2") (pintype "passive"))
      (node (ref "DA3") (pin "3") (pinfunction "VIN_3") (pintype "passive"))
      (node (ref "DA3") (pin "4") (pinfunction "EN_4") (pintype "passive"))
      (node (ref "L11") (pin "2") (pinfunction "2_2") (pintype "passive"))
      (node (ref "R17") (pin "1") (pinfunction "1_1") (pintype "passive"))
    )
    (net (code "75") (name "Net-(DA3-PG)") (class "Default")
      (node (ref "DA3") (pin "5") (pinfunction "PG_5") (pintype "passive"))
      (node (ref "R17") (pin "2") (pinfunction "2_2") (pintype "passive"))
    )
    (net (code "76") (name "Net-(DA3-SS)") (class "Default")
      (node (ref "C72") (pin "1") (pinfunction "1_1") (pintype "passive"))
      (node (ref "DA3") (pin "7") (pinfunction "SS_7") (pintype "passive"))
    )
    (net (code "77") (name "Net-(DA4-ADJ)") (class "Default")
      (node (ref "DA4") (pin "9") (pinfunction "ADJ_9") (pintype "passive"))
      (node (ref "R23") (pin "2") (pinfunction "2_2") (pintype "passive"))
      (node (ref "R24") (pin "1") (pinfunction "1_1") (pintype "passive"))
    )
    (net (code "78") (name "Net-(DA4-EN)") (class "Default")
      (node (ref "C80") (pin "1") (pinfunction "1_1") (pintype "passive"))
      (node (ref "C82") (pin "1") (pinfunction "1_1") (pintype "passive"))
      (node (ref "C84") (pin "1") (pinfunction "1_1") (pintype "passive"))
      (node (ref "DA4") (pin "1") (pinfunction "VIN_1") (pintype "passive"))
      (node (ref "DA4") (pin "15") (pinfunction "VIN_15") (pintype "passive"))
      (node (ref "DA4") (pin "16") (pinfunction "VIN_16") (pintype "passive"))
      (node (ref "DA4") (pin "2") (pinfunction "VIN_2") (pintype "passive"))
      (node (ref "DA4") (pin "3") (pinfunction "VIN_3") (pintype "passive"))
      (node (ref "DA4") (pin "4") (pinfunction "EN_4") (pintype "passive"))
      (node (ref "L23") (pin "2") (pinfunction "2_2") (pintype "passive"))
      (node (ref "R22") (pin "1") (pinfunction "1_1") (pintype "passive"))
    )
    (net (code "79") (name "Net-(DA4-PG)") (class "Default")
      (node (ref "DA4") (pin "5") (pinfunction "PG_5") (pintype "passive"))
      (node (ref "R22") (pin "2") (pinfunction "2_2") (pintype "passive"))
    )
    (net (code "80") (name "Net-(DA4-SS)") (class "Default")
      (node (ref "C86") (pin "1") (pinfunction "1_1") (pintype "passive"))
      (node (ref "DA4") (pin "7") (pinfunction "SS_7") (pintype "passive"))
    )
    (net (code "81") (name "Net-(DA5-ADJ)") (class "Default")
      (node (ref "DA5") (pin "9") (pinfunction "ADJ_9") (pintype "passive"))
      (node (ref "R26") (pin "2") (pinfunction "2_2") (pintype "passive"))
      (node (ref "R27") (pin "1") (pinfunction "1_1") (pintype "passive"))
    )
    (net (code "82") (name "Net-(DA5-EN)") (class "Default")
      (node (ref "C90") (pin "1") (pinfunction "1_1") (pintype "passive"))
      (node (ref "C91") (pin "1") (pinfunction "1_1") (pintype "passive"))
      (node (ref "C92") (pin "1") (pinfunction "1_1") (pintype "passive"))
      (node (ref "DA5") (pin "1") (pinfunction "VIN_1") (pintype "passive"))
      (node (ref "DA5") (pin "15") (pinfunction "VIN_15") (pintype "passive"))
      (node (ref "DA5") (pin "16") (pinfunction "VIN_16") (pintype "passive"))
      (node (ref "DA5") (pin "2") (pinfunction "VIN_2") (pintype "passive"))
      (node (ref "DA5") (pin "3") (pinfunction "VIN_3") (pintype "passive"))
      (node (ref "DA5") (pin "4") (pinfunction "EN_4") (pintype "passive"))
      (node (ref "L25") (pin "2") (pinfunction "2_2") (pintype "passive"))
      (node (ref "R25") (pin "1") (pinfunction "1_1") (pintype "passive"))
    )
    (net (code "83") (name "Net-(DA5-PG)") (class "Default")
      (node (ref "DA5") (pin "5") (pinfunction "PG_5") (pintype "passive"))
      (node (ref "R25") (pin "2") (pinfunction "2_2") (pintype "passive"))
    )
    (net (code "84") (name "Net-(DA5-SS)") (class "Default")
      (node (ref "C93") (pin "1") (pinfunction "1_1") (pintype "passive"))
      (node (ref "DA5") (pin "7") (pinfunction "SS_7") (pintype "passive"))
    )
    (net (code "85") (name "unconnected-(DA3-NC-Pad8)") (class "Default")
      (node (ref "DA3") (pin "8") (pinfunction "NC_8") (pintype "passive"))
    )
    (net (code "86") (name "unconnected-(DA4-NC-Pad8)") (class "Default")
      (node (ref "DA4") (pin "8") (pinfunction "NC_8") (pintype "passive"))
    )
    (net (code "87") (name "unconnected-(DA5-NC-Pad8)") (class "Default")
      (node (ref "DA5") (pin "8") (pinfunction "NC_8") (pintype "passive"))
    )
  )
)
